# M506X.net
KiCad netlist of a schematic drawn in EAGLE
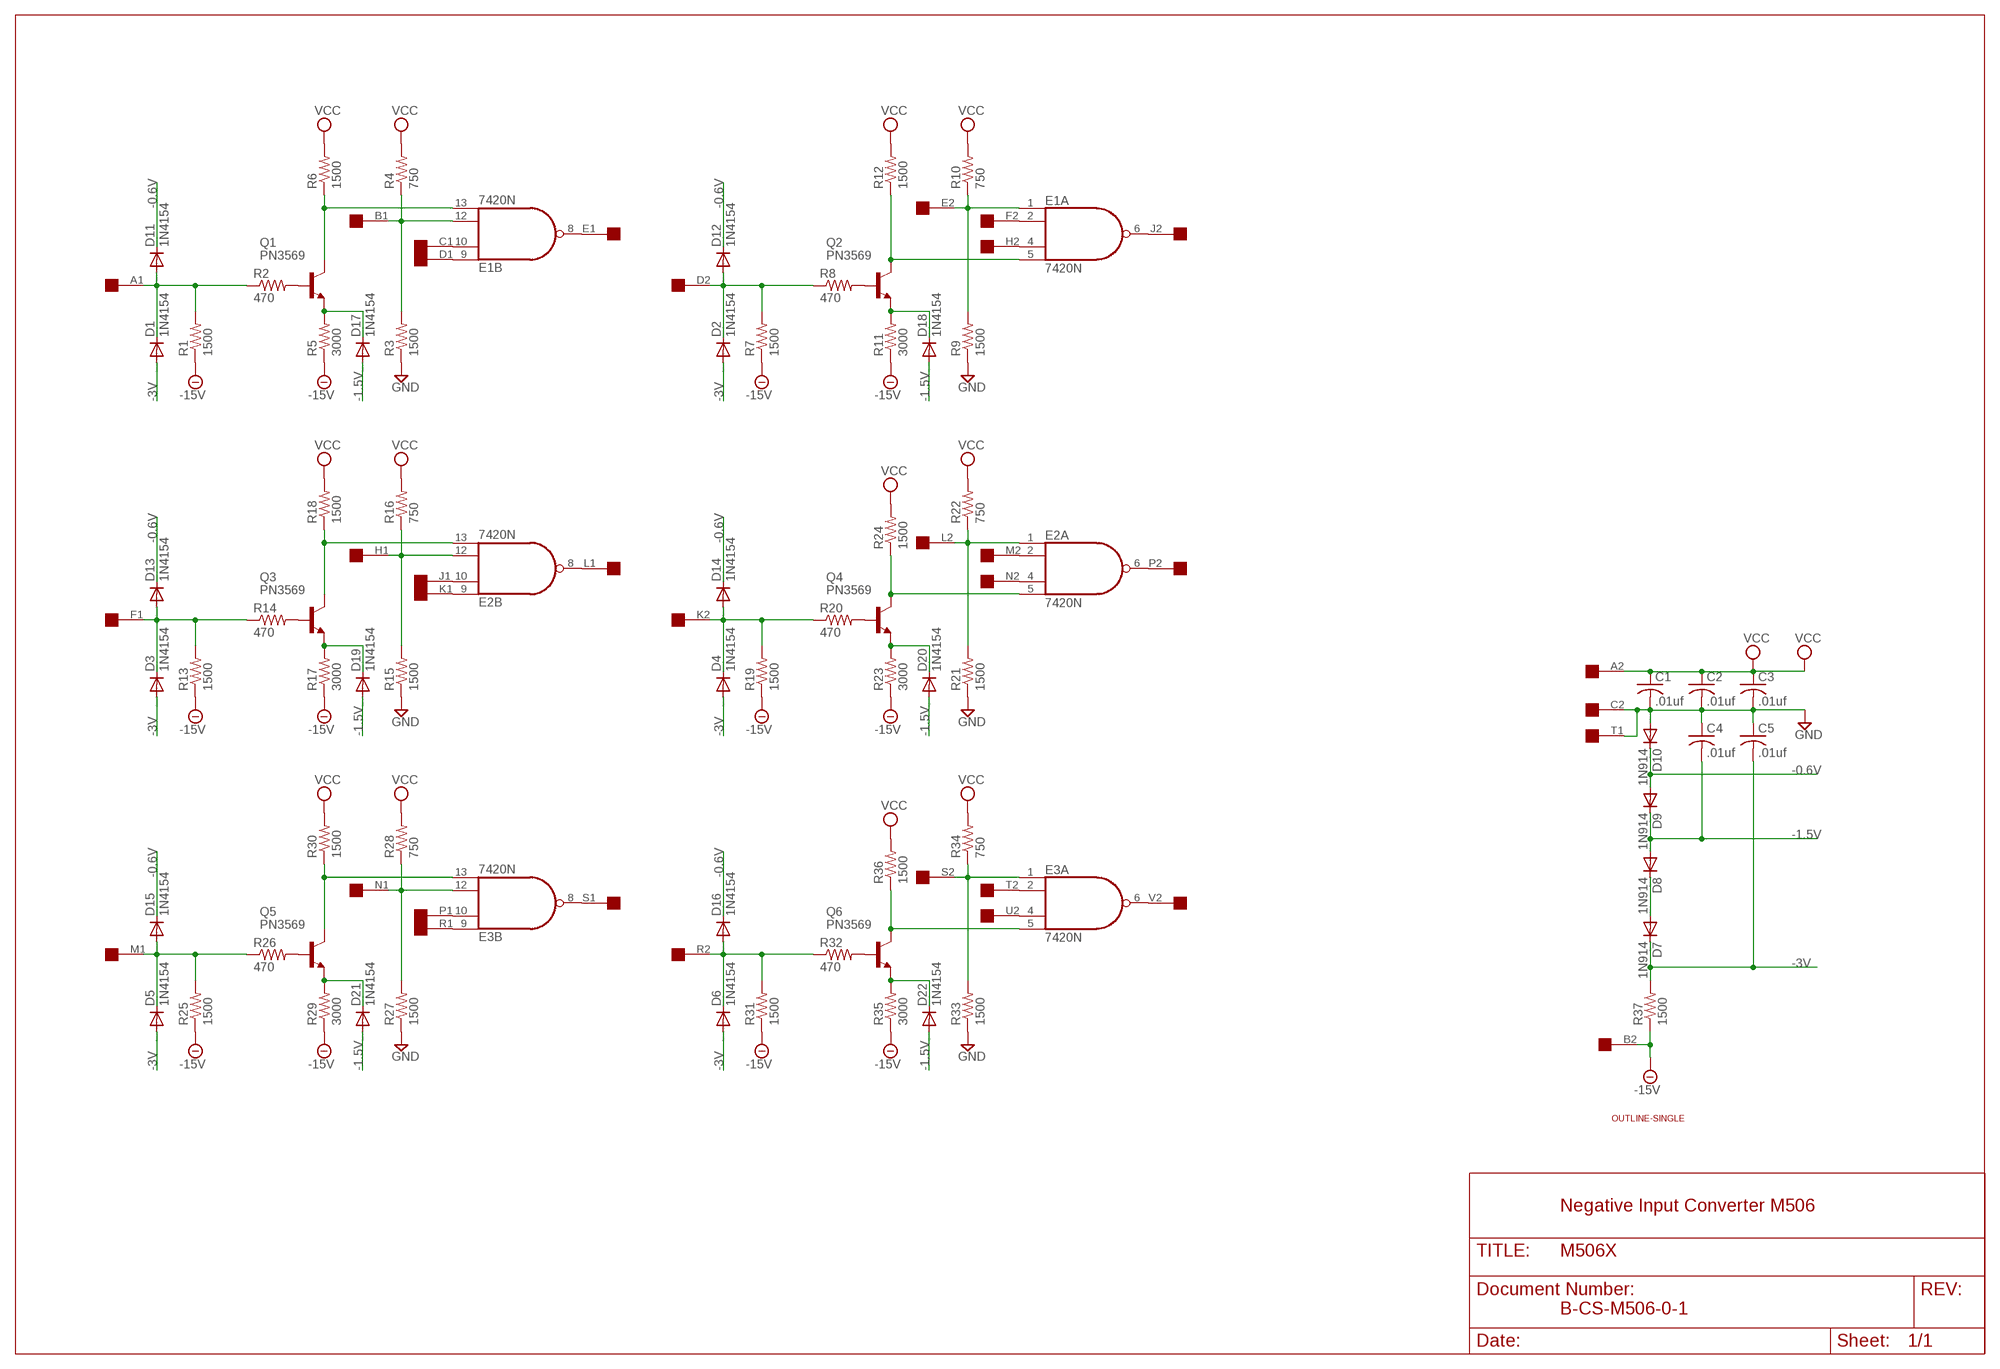
[diagram p0: schematic, sheet 1]

(export (version "E")
  (design (tool "Eeschema 10.0.6"))
  (components
    (comp (ref "C1")
      (value ".01uf")
      (footprint "eagle-import:C050-025X075")
      (libsource (lib "eagle-import") (part "C-US050-025X075"))
    )
    (comp (ref "C2")
      (value ".01uf")
      (footprint "eagle-import:C050-025X075")
      (libsource (lib "eagle-import") (part "C-US050-025X075"))
    )
    (comp (ref "C3")
      (value ".01uf")
      (footprint "eagle-import:C050-025X075")
      (libsource (lib "eagle-import") (part "C-US050-025X075"))
    )
    (comp (ref "C4")
      (value ".01uf")
      (footprint "eagle-import:C050-025X075")
      (libsource (lib "eagle-import") (part "C-US050-025X075"))
    )
    (comp (ref "C5")
      (value ".01uf")
      (footprint "eagle-import:C050-025X075")
      (libsource (lib "eagle-import") (part "C-US050-025X075"))
    )
    (comp (ref "D1")
      (value "1N4154")
      (footprint "eagle-import:DO35-10")
      (libsource (lib "eagle-import") (part "1N4148DO35-10"))
    )
    (comp (ref "D2")
      (value "1N4154")
      (footprint "eagle-import:DO35-10")
      (libsource (lib "eagle-import") (part "1N4148DO35-10"))
    )
    (comp (ref "D3")
      (value "1N4154")
      (footprint "eagle-import:DO35-10")
      (libsource (lib "eagle-import") (part "1N4148DO35-10"))
    )
    (comp (ref "D4")
      (value "1N4154")
      (footprint "eagle-import:DO35-10")
      (libsource (lib "eagle-import") (part "1N4148DO35-10"))
    )
    (comp (ref "D5")
      (value "1N4154")
      (footprint "eagle-import:DO35-10")
      (libsource (lib "eagle-import") (part "1N4148DO35-10"))
    )
    (comp (ref "D6")
      (value "1N4154")
      (footprint "eagle-import:DO35-10")
      (libsource (lib "eagle-import") (part "1N4148DO35-10"))
    )
    (comp (ref "D7")
      (value "1N914")
      (footprint "eagle-import:DO35-10")
      (libsource (lib "eagle-import") (part "1N4148DO35-10"))
    )
    (comp (ref "D8")
      (value "1N914")
      (footprint "eagle-import:DO35-10")
      (libsource (lib "eagle-import") (part "1N4148DO35-10"))
    )
    (comp (ref "D9")
      (value "1N914")
      (footprint "eagle-import:DO35-10")
      (libsource (lib "eagle-import") (part "1N4148DO35-10"))
    )
    (comp (ref "D10")
      (value "1N914")
      (footprint "eagle-import:DO35-10")
      (libsource (lib "eagle-import") (part "1N4148DO35-10"))
    )
    (comp (ref "D11")
      (value "1N4154")
      (footprint "eagle-import:DO35-10")
      (libsource (lib "eagle-import") (part "1N4148DO35-10"))
    )
    (comp (ref "D12")
      (value "1N4154")
      (footprint "eagle-import:DO35-10")
      (libsource (lib "eagle-import") (part "1N4148DO35-10"))
    )
    (comp (ref "D13")
      (value "1N4154")
      (footprint "eagle-import:DO35-10")
      (libsource (lib "eagle-import") (part "1N4148DO35-10"))
    )
    (comp (ref "D14")
      (value "1N4154")
      (footprint "eagle-import:DO35-10")
      (libsource (lib "eagle-import") (part "1N4148DO35-10"))
    )
    (comp (ref "D15")
      (value "1N4154")
      (footprint "eagle-import:DO35-10")
      (libsource (lib "eagle-import") (part "1N4148DO35-10"))
    )
    (comp (ref "D16")
      (value "1N4154")
      (footprint "eagle-import:DO35-10")
      (libsource (lib "eagle-import") (part "1N4148DO35-10"))
    )
    (comp (ref "D17")
      (value "1N4154")
      (footprint "eagle-import:DO35-10")
      (libsource (lib "eagle-import") (part "1N4148DO35-10"))
    )
    (comp (ref "D18")
      (value "1N4154")
      (footprint "eagle-import:DO35-10")
      (libsource (lib "eagle-import") (part "1N4148DO35-10"))
    )
    (comp (ref "D19")
      (value "1N4154")
      (footprint "eagle-import:DO35-10")
      (libsource (lib "eagle-import") (part "1N4148DO35-10"))
    )
    (comp (ref "D20")
      (value "1N4154")
      (footprint "eagle-import:DO35-10")
      (libsource (lib "eagle-import") (part "1N4148DO35-10"))
    )
    (comp (ref "D21")
      (value "1N4154")
      (footprint "eagle-import:DO35-10")
      (libsource (lib "eagle-import") (part "1N4148DO35-10"))
    )
    (comp (ref "D22")
      (value "1N4154")
      (footprint "eagle-import:DO35-10")
      (libsource (lib "eagle-import") (part "1N4148DO35-10"))
    )
    (comp (ref "E1")
      (value "7420N")
      (footprint "eagle-import:DIL14")
      (libsource (lib "eagle-import") (part "7420NS"))
    )
    (comp (ref "E2")
      (value "7420N")
      (footprint "eagle-import:DIL14")
      (libsource (lib "eagle-import") (part "7420NS"))
    )
    (comp (ref "E3")
      (value "7420N")
      (footprint "eagle-import:DIL14")
      (libsource (lib "eagle-import") (part "7420NS"))
    )
    (comp (ref "Q1")
      (value "PN3569")
      (footprint "eagle-import:TO39")
      (libsource (lib "eagle-import") (part "2N3019"))
    )
    (comp (ref "Q2")
      (value "PN3569")
      (footprint "eagle-import:TO39")
      (libsource (lib "eagle-import") (part "2N3019"))
    )
    (comp (ref "Q3")
      (value "PN3569")
      (footprint "eagle-import:TO39")
      (libsource (lib "eagle-import") (part "2N3019"))
    )
    (comp (ref "Q4")
      (value "PN3569")
      (footprint "eagle-import:TO39")
      (libsource (lib "eagle-import") (part "2N3019"))
    )
    (comp (ref "Q5")
      (value "PN3569")
      (footprint "eagle-import:TO39")
      (libsource (lib "eagle-import") (part "2N3019"))
    )
    (comp (ref "Q6")
      (value "PN3569")
      (footprint "eagle-import:TO39")
      (libsource (lib "eagle-import") (part "2N3019"))
    )
    (comp (ref "R1")
      (value "1500")
      (footprint "eagle-import:0207_10")
      (libsource (lib "eagle-import") (part "R-US_0207/10"))
    )
    (comp (ref "R2")
      (value "470")
      (footprint "eagle-import:0207_10")
      (libsource (lib "eagle-import") (part "R-US_0207/10"))
    )
    (comp (ref "R3")
      (value "1500")
      (footprint "eagle-import:0207_10")
      (libsource (lib "eagle-import") (part "R-US_0207/10"))
    )
    (comp (ref "R4")
      (value "750")
      (footprint "eagle-import:0207_10")
      (libsource (lib "eagle-import") (part "R-US_0207/10"))
    )
    (comp (ref "R5")
      (value "3000")
      (footprint "eagle-import:0207_10")
      (libsource (lib "eagle-import") (part "R-US_0207/10"))
    )
    (comp (ref "R6")
      (value "1500")
      (footprint "eagle-import:0207_10")
      (libsource (lib "eagle-import") (part "R-US_0207/10"))
    )
    (comp (ref "R7")
      (value "1500")
      (footprint "eagle-import:0207_10")
      (libsource (lib "eagle-import") (part "R-US_0207/10"))
    )
    (comp (ref "R8")
      (value "470")
      (footprint "eagle-import:0207_10")
      (libsource (lib "eagle-import") (part "R-US_0207/10"))
    )
    (comp (ref "R9")
      (value "1500")
      (footprint "eagle-import:0207_10")
      (libsource (lib "eagle-import") (part "R-US_0207/10"))
    )
    (comp (ref "R10")
      (value "750")
      (footprint "eagle-import:0207_10")
      (libsource (lib "eagle-import") (part "R-US_0207/10"))
    )
    (comp (ref "R11")
      (value "3000")
      (footprint "eagle-import:0207_10")
      (libsource (lib "eagle-import") (part "R-US_0207/10"))
    )
    (comp (ref "R12")
      (value "1500")
      (footprint "eagle-import:0207_10")
      (libsource (lib "eagle-import") (part "R-US_0207/10"))
    )
    (comp (ref "R13")
      (value "1500")
      (footprint "eagle-import:0207_10")
      (libsource (lib "eagle-import") (part "R-US_0207/10"))
    )
    (comp (ref "R14")
      (value "470")
      (footprint "eagle-import:0207_10")
      (libsource (lib "eagle-import") (part "R-US_0207/10"))
    )
    (comp (ref "R15")
      (value "1500")
      (footprint "eagle-import:0207_10")
      (libsource (lib "eagle-import") (part "R-US_0207/10"))
    )
    (comp (ref "R16")
      (value "750")
      (footprint "eagle-import:0207_10")
      (libsource (lib "eagle-import") (part "R-US_0207/10"))
    )
    (comp (ref "R17")
      (value "3000")
      (footprint "eagle-import:0207_10")
      (libsource (lib "eagle-import") (part "R-US_0207/10"))
    )
    (comp (ref "R18")
      (value "1500")
      (footprint "eagle-import:0207_10")
      (libsource (lib "eagle-import") (part "R-US_0207/10"))
    )
    (comp (ref "R19")
      (value "1500")
      (footprint "eagle-import:0207_10")
      (libsource (lib "eagle-import") (part "R-US_0207/10"))
    )
    (comp (ref "R20")
      (value "470")
      (footprint "eagle-import:0207_10")
      (libsource (lib "eagle-import") (part "R-US_0207/10"))
    )
    (comp (ref "R21")
      (value "1500")
      (footprint "eagle-import:0207_10")
      (libsource (lib "eagle-import") (part "R-US_0207/10"))
    )
    (comp (ref "R22")
      (value "750")
      (footprint "eagle-import:0207_10")
      (libsource (lib "eagle-import") (part "R-US_0207/10"))
    )
    (comp (ref "R23")
      (value "3000")
      (footprint "eagle-import:0207_10")
      (libsource (lib "eagle-import") (part "R-US_0207/10"))
    )
    (comp (ref "R24")
      (value "1500")
      (footprint "eagle-import:0207_10")
      (libsource (lib "eagle-import") (part "R-US_0207/10"))
    )
    (comp (ref "R25")
      (value "1500")
      (footprint "eagle-import:0207_10")
      (libsource (lib "eagle-import") (part "R-US_0207/10"))
    )
    (comp (ref "R26")
      (value "470")
      (footprint "eagle-import:0207_10")
      (libsource (lib "eagle-import") (part "R-US_0207/10"))
    )
    (comp (ref "R27")
      (value "1500")
      (footprint "eagle-import:0207_10")
      (libsource (lib "eagle-import") (part "R-US_0207/10"))
    )
    (comp (ref "R28")
      (value "750")
      (footprint "eagle-import:0207_10")
      (libsource (lib "eagle-import") (part "R-US_0207/10"))
    )
    (comp (ref "R29")
      (value "3000")
      (footprint "eagle-import:0207_10")
      (libsource (lib "eagle-import") (part "R-US_0207/10"))
    )
    (comp (ref "R30")
      (value "1500")
      (footprint "eagle-import:0207_10")
      (libsource (lib "eagle-import") (part "R-US_0207/10"))
    )
    (comp (ref "R31")
      (value "1500")
      (footprint "eagle-import:0207_10")
      (libsource (lib "eagle-import") (part "R-US_0207/10"))
    )
    (comp (ref "R32")
      (value "470")
      (footprint "eagle-import:0207_10")
      (libsource (lib "eagle-import") (part "R-US_0207/10"))
    )
    (comp (ref "R33")
      (value "1500")
      (footprint "eagle-import:0207_10")
      (libsource (lib "eagle-import") (part "R-US_0207/10"))
    )
    (comp (ref "R34")
      (value "750")
      (footprint "eagle-import:0207_10")
      (libsource (lib "eagle-import") (part "R-US_0207/10"))
    )
    (comp (ref "R35")
      (value "3000")
      (footprint "eagle-import:0207_10")
      (libsource (lib "eagle-import") (part "R-US_0207/10"))
    )
    (comp (ref "R36")
      (value "1500")
      (footprint "eagle-import:0207_10")
      (libsource (lib "eagle-import") (part "R-US_0207/10"))
    )
    (comp (ref "R37")
      (value "1500")
      (footprint "eagle-import:0207_10")
      (libsource (lib "eagle-import") (part "R-US_0207/10"))
    )
    (comp (ref "U$2")
      (value "SINGLE")
      (footprint "eagle-import:EDGE-CON2")
      (libsource (lib "eagle-import") (part "SINGLE"))
    )
    (comp (ref "U$4")
      (value "OUTLINE-SINGLE")
      (footprint "eagle-import:SINGLE")
      (libsource (lib "eagle-import") (part "OUTLINE-SINGLE"))
    )
  )
  (nets
    (net (code "1") (name "-15V") (class "Default")
      (node (ref "R1") (pin "1") (pinfunction "1_1") (pintype "passive"))
      (node (ref "R11") (pin "1") (pinfunction "1_1") (pintype "passive"))
      (node (ref "R13") (pin "1") (pinfunction "1_1") (pintype "passive"))
      (node (ref "R17") (pin "1") (pinfunction "1_1") (pintype "passive"))
      (node (ref "R19") (pin "1") (pinfunction "1_1") (pintype "passive"))
      (node (ref "R23") (pin "1") (pinfunction "1_1") (pintype "passive"))
      (node (ref "R25") (pin "1") (pinfunction "1_1") (pintype "passive"))
      (node (ref "R29") (pin "1") (pinfunction "1_1") (pintype "passive"))
      (node (ref "R31") (pin "1") (pinfunction "1_1") (pintype "passive"))
      (node (ref "R35") (pin "1") (pinfunction "1_1") (pintype "passive"))
      (node (ref "R37") (pin "1") (pinfunction "1_1") (pintype "passive"))
      (node (ref "R5") (pin "1") (pinfunction "1_1") (pintype "passive"))
      (node (ref "R7") (pin "1") (pinfunction "1_1") (pintype "passive"))
      (node (ref "U$2") (pin "B2") (pinfunction "1_B2") (pintype "bidirectional"))
    )
    (net (code "2") (name "/-0.6V") (class "Default")
      (node (ref "D10") (pin "C") (pinfunction "C_C") (pintype "passive"))
      (node (ref "D11") (pin "C") (pinfunction "C_C") (pintype "passive"))
      (node (ref "D12") (pin "C") (pinfunction "C_C") (pintype "passive"))
      (node (ref "D13") (pin "C") (pinfunction "C_C") (pintype "passive"))
      (node (ref "D14") (pin "C") (pinfunction "C_C") (pintype "passive"))
      (node (ref "D15") (pin "C") (pinfunction "C_C") (pintype "passive"))
      (node (ref "D16") (pin "C") (pinfunction "C_C") (pintype "passive"))
      (node (ref "D9") (pin "A") (pinfunction "A_A") (pintype "passive"))
    )
    (net (code "3") (name "/-1.5V") (class "Default")
      (node (ref "C4") (pin "2") (pinfunction "2_2") (pintype "passive"))
      (node (ref "D17") (pin "A") (pinfunction "A_A") (pintype "passive"))
      (node (ref "D18") (pin "A") (pinfunction "A_A") (pintype "passive"))
      (node (ref "D19") (pin "A") (pinfunction "A_A") (pintype "passive"))
      (node (ref "D20") (pin "A") (pinfunction "A_A") (pintype "passive"))
      (node (ref "D21") (pin "A") (pinfunction "A_A") (pintype "passive"))
      (node (ref "D22") (pin "A") (pinfunction "A_A") (pintype "passive"))
      (node (ref "D8") (pin "A") (pinfunction "A_A") (pintype "passive"))
      (node (ref "D9") (pin "C") (pinfunction "C_C") (pintype "passive"))
    )
    (net (code "4") (name "/-3V") (class "Default")
      (node (ref "C5") (pin "2") (pinfunction "2_2") (pintype "passive"))
      (node (ref "D1") (pin "A") (pinfunction "A_A") (pintype "passive"))
      (node (ref "D2") (pin "A") (pinfunction "A_A") (pintype "passive"))
      (node (ref "D3") (pin "A") (pinfunction "A_A") (pintype "passive"))
      (node (ref "D4") (pin "A") (pinfunction "A_A") (pintype "passive"))
      (node (ref "D5") (pin "A") (pinfunction "A_A") (pintype "passive"))
      (node (ref "D6") (pin "A") (pinfunction "A_A") (pintype "passive"))
      (node (ref "D7") (pin "C") (pinfunction "C_C") (pintype "passive"))
      (node (ref "R37") (pin "2") (pinfunction "2_2") (pintype "passive"))
    )
    (net (code "5") (name "GND") (class "Default")
      (node (ref "C1") (pin "2") (pinfunction "2_2") (pintype "passive"))
      (node (ref "C2") (pin "2") (pinfunction "2_2") (pintype "passive"))
      (node (ref "C3") (pin "2") (pinfunction "2_2") (pintype "passive"))
      (node (ref "C4") (pin "1") (pinfunction "1_1") (pintype "passive"))
      (node (ref "C5") (pin "1") (pinfunction "1_1") (pintype "passive"))
      (node (ref "D10") (pin "A") (pinfunction "A_A") (pintype "passive"))
      (node (ref "R15") (pin "1") (pinfunction "1_1") (pintype "passive"))
      (node (ref "R21") (pin "1") (pinfunction "1_1") (pintype "passive"))
      (node (ref "R27") (pin "1") (pinfunction "1_1") (pintype "passive"))
      (node (ref "R3") (pin "1") (pinfunction "1_1") (pintype "passive"))
      (node (ref "R33") (pin "1") (pinfunction "1_1") (pintype "passive"))
      (node (ref "R9") (pin "1") (pinfunction "1_1") (pintype "passive"))
      (node (ref "U$2") (pin "C2") (pinfunction "1_C2") (pintype "bidirectional"))
      (node (ref "U$2") (pin "T1") (pinfunction "1_T1") (pintype "bidirectional"))
    )
    (net (code "6") (name "Net-(D7-PadA)") (class "Default")
      (node (ref "D7") (pin "A") (pinfunction "A_A") (pintype "passive"))
      (node (ref "D8") (pin "C") (pinfunction "C_C") (pintype "passive"))
    )
    (net (code "7") (name "Net-(E1A-I0)") (class "Default")
      (node (ref "E1") (pin "1") (pinfunction "I0_1") (pintype "input"))
      (node (ref "R10") (pin "1") (pinfunction "1_1") (pintype "passive"))
      (node (ref "R9") (pin "2") (pinfunction "2_2") (pintype "passive"))
      (node (ref "U$2") (pin "E2") (pinfunction "1_E2") (pintype "bidirectional"))
    )
    (net (code "8") (name "Net-(E1A-I1)") (class "Default")
      (node (ref "E1") (pin "2") (pinfunction "I1_2") (pintype "input"))
      (node (ref "U$2") (pin "F2") (pinfunction "1_F2") (pintype "bidirectional"))
    )
    (net (code "9") (name "Net-(E1A-I2)") (class "Default")
      (node (ref "E1") (pin "4") (pinfunction "I2_4") (pintype "input"))
      (node (ref "U$2") (pin "H2") (pinfunction "1_H2") (pintype "bidirectional"))
    )
    (net (code "10") (name "Net-(E1A-I3)") (class "Default")
      (node (ref "E1") (pin "5") (pinfunction "I3_5") (pintype "input"))
      (node (ref "Q2") (pin "3") (pinfunction "C_3") (pintype "passive"))
      (node (ref "R12") (pin "1") (pinfunction "1_1") (pintype "passive"))
    )
    (net (code "11") (name "Net-(E1A-O)") (class "Default")
      (node (ref "E1") (pin "6") (pinfunction "O_6") (pintype "output"))
      (node (ref "U$2") (pin "J2") (pinfunction "1_J2") (pintype "bidirectional"))
    )
    (net (code "12") (name "Net-(E1B-I0)") (class "Default")
      (node (ref "E1") (pin "9") (pinfunction "I0_9") (pintype "input"))
      (node (ref "U$2") (pin "D1") (pinfunction "1_D1") (pintype "bidirectional"))
    )
    (net (code "13") (name "Net-(E1B-I1)") (class "Default")
      (node (ref "E1") (pin "10") (pinfunction "I1_10") (pintype "input"))
      (node (ref "U$2") (pin "C1") (pinfunction "1_C1") (pintype "bidirectional"))
    )
    (net (code "14") (name "Net-(E1B-I2)") (class "Default")
      (node (ref "E1") (pin "12") (pinfunction "I2_12") (pintype "input"))
      (node (ref "R3") (pin "2") (pinfunction "2_2") (pintype "passive"))
      (node (ref "R4") (pin "1") (pinfunction "1_1") (pintype "passive"))
      (node (ref "U$2") (pin "B1") (pinfunction "1_B1") (pintype "bidirectional"))
    )
    (net (code "15") (name "Net-(E1B-I3)") (class "Default")
      (node (ref "E1") (pin "13") (pinfunction "I3_13") (pintype "input"))
      (node (ref "Q1") (pin "3") (pinfunction "C_3") (pintype "passive"))
      (node (ref "R6") (pin "1") (pinfunction "1_1") (pintype "passive"))
    )
    (net (code "16") (name "Net-(E1B-O)") (class "Default")
      (node (ref "E1") (pin "8") (pinfunction "O_8") (pintype "output"))
      (node (ref "U$2") (pin "E1") (pinfunction "1_E1") (pintype "bidirectional"))
    )
    (net (code "17") (name "Net-(E2A-I0)") (class "Default")
      (node (ref "E2") (pin "1") (pinfunction "I0_1") (pintype "input"))
      (node (ref "R21") (pin "2") (pinfunction "2_2") (pintype "passive"))
      (node (ref "R22") (pin "1") (pinfunction "1_1") (pintype "passive"))
      (node (ref "U$2") (pin "L2") (pinfunction "1_L2") (pintype "bidirectional"))
    )
    (net (code "18") (name "Net-(E2A-I1)") (class "Default")
      (node (ref "E2") (pin "2") (pinfunction "I1_2") (pintype "input"))
      (node (ref "U$2") (pin "M2") (pinfunction "1_M2") (pintype "bidirectional"))
    )
    (net (code "19") (name "Net-(E2A-I2)") (class "Default")
      (node (ref "E2") (pin "4") (pinfunction "I2_4") (pintype "input"))
      (node (ref "U$2") (pin "N2") (pinfunction "1_N2") (pintype "bidirectional"))
    )
    (net (code "20") (name "Net-(E2A-I3)") (class "Default")
      (node (ref "E2") (pin "5") (pinfunction "I3_5") (pintype "input"))
      (node (ref "Q4") (pin "3") (pinfunction "C_3") (pintype "passive"))
      (node (ref "R24") (pin "1") (pinfunction "1_1") (pintype "passive"))
    )
    (net (code "21") (name "Net-(E2A-O)") (class "Default")
      (node (ref "E2") (pin "6") (pinfunction "O_6") (pintype "output"))
      (node (ref "U$2") (pin "P2") (pinfunction "1_P2") (pintype "bidirectional"))
    )
    (net (code "22") (name "Net-(E2B-I0)") (class "Default")
      (node (ref "E2") (pin "9") (pinfunction "I0_9") (pintype "input"))
      (node (ref "U$2") (pin "K1") (pinfunction "1_K1") (pintype "bidirectional"))
    )
    (net (code "23") (name "Net-(E2B-I1)") (class "Default")
      (node (ref "E2") (pin "10") (pinfunction "I1_10") (pintype "input"))
      (node (ref "U$2") (pin "J1") (pinfunction "1_J1") (pintype "bidirectional"))
    )
    (net (code "24") (name "Net-(E2B-I2)") (class "Default")
      (node (ref "E2") (pin "12") (pinfunction "I2_12") (pintype "input"))
      (node (ref "R15") (pin "2") (pinfunction "2_2") (pintype "passive"))
      (node (ref "R16") (pin "1") (pinfunction "1_1") (pintype "passive"))
      (node (ref "U$2") (pin "H1") (pinfunction "1_H1") (pintype "bidirectional"))
    )
    (net (code "25") (name "Net-(E2B-I3)") (class "Default")
      (node (ref "E2") (pin "13") (pinfunction "I3_13") (pintype "input"))
      (node (ref "Q3") (pin "3") (pinfunction "C_3") (pintype "passive"))
      (node (ref "R18") (pin "1") (pinfunction "1_1") (pintype "passive"))
    )
    (net (code "26") (name "Net-(E2B-O)") (class "Default")
      (node (ref "E2") (pin "8") (pinfunction "O_8") (pintype "output"))
      (node (ref "U$2") (pin "L1") (pinfunction "1_L1") (pintype "bidirectional"))
    )
    (net (code "27") (name "Net-(E3A-I0)") (class "Default")
      (node (ref "E3") (pin "1") (pinfunction "I0_1") (pintype "input"))
      (node (ref "R33") (pin "2") (pinfunction "2_2") (pintype "passive"))
      (node (ref "R34") (pin "1") (pinfunction "1_1") (pintype "passive"))
      (node (ref "U$2") (pin "S2") (pinfunction "1_S2") (pintype "bidirectional"))
    )
    (net (code "28") (name "Net-(E3A-I1)") (class "Default")
      (node (ref "E3") (pin "2") (pinfunction "I1_2") (pintype "input"))
      (node (ref "U$2") (pin "T2") (pinfunction "1_T2") (pintype "bidirectional"))
    )
    (net (code "29") (name "Net-(E3A-I2)") (class "Default")
      (node (ref "E3") (pin "4") (pinfunction "I2_4") (pintype "input"))
      (node (ref "U$2") (pin "U2") (pinfunction "1_U2") (pintype "bidirectional"))
    )
    (net (code "30") (name "Net-(E3A-I3)") (class "Default")
      (node (ref "E3") (pin "5") (pinfunction "I3_5") (pintype "input"))
      (node (ref "Q6") (pin "3") (pinfunction "C_3") (pintype "passive"))
      (node (ref "R36") (pin "1") (pinfunction "1_1") (pintype "passive"))
    )
    (net (code "31") (name "Net-(E3A-O)") (class "Default")
      (node (ref "E3") (pin "6") (pinfunction "O_6") (pintype "output"))
      (node (ref "U$2") (pin "V2") (pinfunction "1_V2") (pintype "bidirectional"))
    )
    (net (code "32") (name "Net-(E3B-I0)") (class "Default")
      (node (ref "E3") (pin "9") (pinfunction "I0_9") (pintype "input"))
      (node (ref "U$2") (pin "R1") (pinfunction "1_R1") (pintype "bidirectional"))
    )
    (net (code "33") (name "Net-(E3B-I1)") (class "Default")
      (node (ref "E3") (pin "10") (pinfunction "I1_10") (pintype "input"))
      (node (ref "U$2") (pin "P1") (pinfunction "1_P1") (pintype "bidirectional"))
    )
    (net (code "34") (name "Net-(E3B-I2)") (class "Default")
      (node (ref "E3") (pin "12") (pinfunction "I2_12") (pintype "input"))
      (node (ref "R27") (pin "2") (pinfunction "2_2") (pintype "passive"))
      (node (ref "R28") (pin "1") (pinfunction "1_1") (pintype "passive"))
      (node (ref "U$2") (pin "N1") (pinfunction "1_N1") (pintype "bidirectional"))
    )
    (net (code "35") (name "Net-(E3B-I3)") (class "Default")
      (node (ref "E3") (pin "13") (pinfunction "I3_13") (pintype "input"))
      (node (ref "Q5") (pin "3") (pinfunction "C_3") (pintype "passive"))
      (node (ref "R30") (pin "1") (pinfunction "1_1") (pintype "passive"))
    )
    (net (code "36") (name "Net-(E3B-O)") (class "Default")
      (node (ref "E3") (pin "8") (pinfunction "O_8") (pintype "output"))
      (node (ref "U$2") (pin "S1") (pinfunction "1_S1") (pintype "bidirectional"))
    )
    (net (code "37") (name "Net-(Q1-B)") (class "Default")
      (node (ref "Q1") (pin "2") (pinfunction "B_2") (pintype "passive"))
      (node (ref "R2") (pin "2") (pinfunction "2_2") (pintype "passive"))
    )
    (net (code "38") (name "Net-(Q1-E)") (class "Default")
      (node (ref "D17") (pin "C") (pinfunction "C_C") (pintype "passive"))
      (node (ref "Q1") (pin "1") (pinfunction "E_1") (pintype "passive"))
      (node (ref "R5") (pin "2") (pinfunction "2_2") (pintype "passive"))
    )
    (net (code "39") (name "Net-(Q2-B)") (class "Default")
      (node (ref "Q2") (pin "2") (pinfunction "B_2") (pintype "passive"))
      (node (ref "R8") (pin "2") (pinfunction "2_2") (pintype "passive"))
    )
    (net (code "40") (name "Net-(Q2-E)") (class "Default")
      (node (ref "D18") (pin "C") (pinfunction "C_C") (pintype "passive"))
      (node (ref "Q2") (pin "1") (pinfunction "E_1") (pintype "passive"))
      (node (ref "R11") (pin "2") (pinfunction "2_2") (pintype "passive"))
    )
    (net (code "41") (name "Net-(Q3-B)") (class "Default")
      (node (ref "Q3") (pin "2") (pinfunction "B_2") (pintype "passive"))
      (node (ref "R14") (pin "2") (pinfunction "2_2") (pintype "passive"))
    )
    (net (code "42") (name "Net-(Q3-E)") (class "Default")
      (node (ref "D19") (pin "C") (pinfunction "C_C") (pintype "passive"))
      (node (ref "Q3") (pin "1") (pinfunction "E_1") (pintype "passive"))
      (node (ref "R17") (pin "2") (pinfunction "2_2") (pintype "passive"))
    )
    (net (code "43") (name "Net-(Q4-B)") (class "Default")
      (node (ref "Q4") (pin "2") (pinfunction "B_2") (pintype "passive"))
      (node (ref "R20") (pin "2") (pinfunction "2_2") (pintype "passive"))
    )
    (net (code "44") (name "Net-(Q4-E)") (class "Default")
      (node (ref "D20") (pin "C") (pinfunction "C_C") (pintype "passive"))
      (node (ref "Q4") (pin "1") (pinfunction "E_1") (pintype "passive"))
      (node (ref "R23") (pin "2") (pinfunction "2_2") (pintype "passive"))
    )
    (net (code "45") (name "Net-(Q5-B)") (class "Default")
      (node (ref "Q5") (pin "2") (pinfunction "B_2") (pintype "passive"))
      (node (ref "R26") (pin "2") (pinfunction "2_2") (pintype "passive"))
    )
    (net (code "46") (name "Net-(Q5-E)") (class "Default")
      (node (ref "D21") (pin "C") (pinfunction "C_C") (pintype "passive"))
      (node (ref "Q5") (pin "1") (pinfunction "E_1") (pintype "passive"))
      (node (ref "R29") (pin "2") (pinfunction "2_2") (pintype "passive"))
    )
    (net (code "47") (name "Net-(Q6-B)") (class "Default")
      (node (ref "Q6") (pin "2") (pinfunction "B_2") (pintype "passive"))
      (node (ref "R32") (pin "2") (pinfunction "2_2") (pintype "passive"))
    )
    (net (code "48") (name "Net-(Q6-E)") (class "Default")
      (node (ref "D22") (pin "C") (pinfunction "C_C") (pintype "passive"))
      (node (ref "Q6") (pin "1") (pinfunction "E_1") (pintype "passive"))
      (node (ref "R35") (pin "2") (pinfunction "2_2") (pintype "passive"))
    )
    (net (code "49") (name "Net-(U$2A-1)") (class "Default")
      (node (ref "D1") (pin "C") (pinfunction "C_C") (pintype "passive"))
      (node (ref "D11") (pin "A") (pinfunction "A_A") (pintype "passive"))
      (node (ref "R1") (pin "2") (pinfunction "2_2") (pintype "passive"))
      (node (ref "R2") (pin "1") (pinfunction "1_1") (pintype "passive"))
      (node (ref "U$2") (pin "A1") (pinfunction "1_A1") (pintype "bidirectional"))
    )
    (net (code "50") (name "Net-(U$2AB-1)") (class "Default")
      (node (ref "D16") (pin "A") (pinfunction "A_A") (pintype "passive"))
      (node (ref "D6") (pin "C") (pinfunction "C_C") (pintype "passive"))
      (node (ref "R31") (pin "2") (pinfunction "2_2") (pintype "passive"))
      (node (ref "R32") (pin "1") (pinfunction "1_1") (pintype "passive"))
      (node (ref "U$2") (pin "R2") (pinfunction "1_R2") (pintype "bidirectional"))
    )
    (net (code "51") (name "Net-(U$2H-1)") (class "Default")
      (node (ref "D12") (pin "A") (pinfunction "A_A") (pintype "passive"))
      (node (ref "D2") (pin "C") (pinfunction "C_C") (pintype "passive"))
      (node (ref "R7") (pin "2") (pinfunction "2_2") (pintype "passive"))
      (node (ref "R8") (pin "1") (pinfunction "1_1") (pintype "passive"))
      (node (ref "U$2") (pin "D2") (pinfunction "1_D2") (pintype "bidirectional"))
    )
    (net (code "52") (name "Net-(U$2K-1)") (class "Default")
      (node (ref "D13") (pin "A") (pinfunction "A_A") (pintype "passive"))
      (node (ref "D3") (pin "C") (pinfunction "C_C") (pintype "passive"))
      (node (ref "R13") (pin "2") (pinfunction "2_2") (pintype "passive"))
      (node (ref "R14") (pin "1") (pinfunction "1_1") (pintype "passive"))
      (node (ref "U$2") (pin "F1") (pinfunction "1_F1") (pintype "bidirectional"))
    )
    (net (code "53") (name "Net-(U$2R-1)") (class "Default")
      (node (ref "D14") (pin "A") (pinfunction "A_A") (pintype "passive"))
      (node (ref "D4") (pin "C") (pinfunction "C_C") (pintype "passive"))
      (node (ref "R19") (pin "2") (pinfunction "2_2") (pintype "passive"))
      (node (ref "R20") (pin "1") (pinfunction "1_1") (pintype "passive"))
      (node (ref "U$2") (pin "K2") (pinfunction "1_K2") (pintype "bidirectional"))
    )
    (net (code "54") (name "Net-(U$2U-1)") (class "Default")
      (node (ref "D15") (pin "A") (pinfunction "A_A") (pintype "passive"))
      (node (ref "D5") (pin "C") (pinfunction "C_C") (pintype "passive"))
      (node (ref "R25") (pin "2") (pinfunction "2_2") (pintype "passive"))
      (node (ref "R26") (pin "1") (pinfunction "1_1") (pintype "passive"))
      (node (ref "U$2") (pin "M1") (pinfunction "1_M1") (pintype "bidirectional"))
    )
    (net (code "55") (name "VCC") (class "Default")
      (node (ref "C1") (pin "1") (pinfunction "1_1") (pintype "passive"))
      (node (ref "C2") (pin "1") (pinfunction "1_1") (pintype "passive"))
      (node (ref "C3") (pin "1") (pinfunction "1_1") (pintype "passive"))
      (node (ref "R10") (pin "2") (pinfunction "2_2") (pintype "passive"))
      (node (ref "R12") (pin "2") (pinfunction "2_2") (pintype "passive"))
      (node (ref "R16") (pin "2") (pinfunction "2_2") (pintype "passive"))
      (node (ref "R18") (pin "2") (pinfunction "2_2") (pintype "passive"))
      (node (ref "R22") (pin "2") (pinfunction "2_2") (pintype "passive"))
      (node (ref "R24") (pin "2") (pinfunction "2_2") (pintype "passive"))
      (node (ref "R28") (pin "2") (pinfunction "2_2") (pintype "passive"))
      (node (ref "R30") (pin "2") (pinfunction "2_2") (pintype "passive"))
      (node (ref "R34") (pin "2") (pinfunction "2_2") (pintype "passive"))
      (node (ref "R36") (pin "2") (pinfunction "2_2") (pintype "passive"))
      (node (ref "R4") (pin "2") (pinfunction "2_2") (pintype "passive"))
      (node (ref "R6") (pin "2") (pinfunction "2_2") (pintype "passive"))
      (node (ref "U$2") (pin "A2") (pinfunction "1_A2") (pintype "bidirectional"))
    )
  )
)
